# vcf.net
KiCad netlist of a schematic drawn in EAGLE
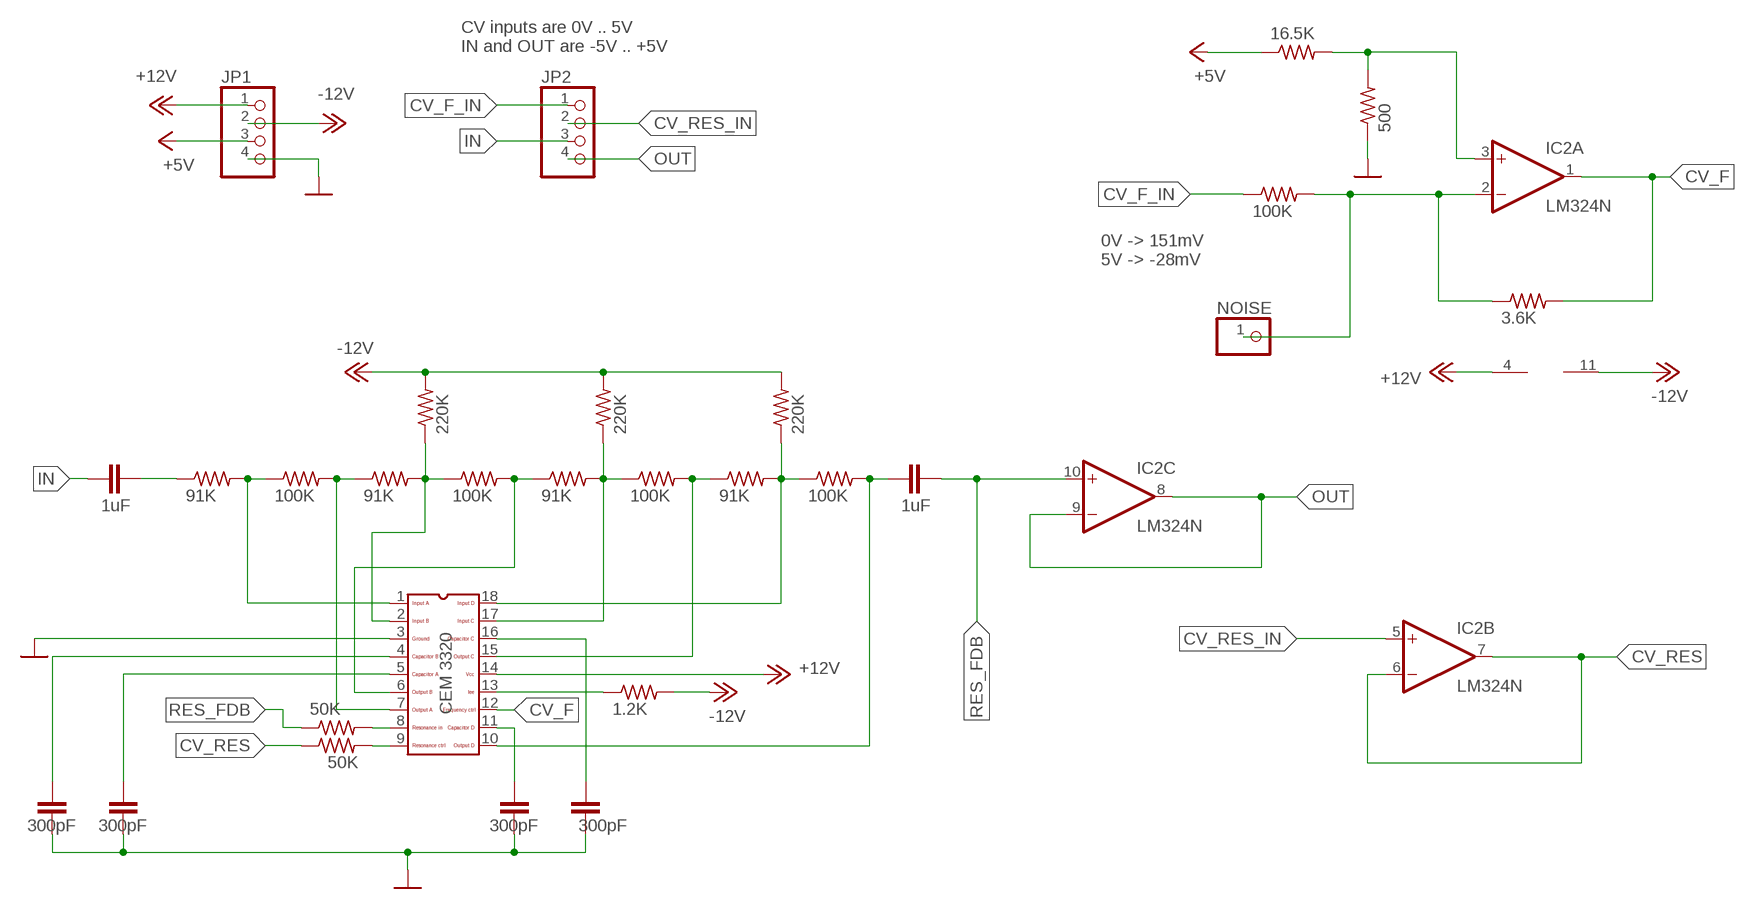
[diagram p0: schematic, sheet 1]

(export (version "E")
  (design (tool "Eeschema 10.0.6"))
  (components
    (comp (ref "C1")
      (value "300pF")
      (footprint "eagle-import:C025-030X050")
      (libsource (lib "eagle-import") (part "C-EU025-030X050"))
    )
    (comp (ref "C2")
      (value "300pF")
      (footprint "eagle-import:C025-030X050")
      (libsource (lib "eagle-import") (part "C-EU025-030X050"))
    )
    (comp (ref "C3")
      (value "300pF")
      (footprint "eagle-import:C025-030X050")
      (libsource (lib "eagle-import") (part "C-EU025-030X050"))
    )
    (comp (ref "C4")
      (value "300pF")
      (footprint "eagle-import:C025-030X050")
      (libsource (lib "eagle-import") (part "C-EU025-030X050"))
    )
    (comp (ref "C5")
      (value "1uF")
      (footprint "eagle-import:C025-030X050")
      (libsource (lib "eagle-import") (part "C-EU025-030X050"))
    )
    (comp (ref "C6")
      (value "1uF")
      (footprint "eagle-import:C025-030X050")
      (libsource (lib "eagle-import") (part "C-EU025-030X050"))
    )
    (comp (ref "IC1")
      (value "CEM3320")
      (footprint "eagle-import:DIL18")
      (libsource (lib "eagle-import") (part "CEM3320"))
    )
    (comp (ref "IC2")
      (value "LM324N")
      (footprint "eagle-import:DIL14")
      (libsource (lib "eagle-import") (part "LM324N"))
    )
    (comp (ref "JP1")
      (value "PINHD-1X4")
      (footprint "eagle-import:1X04")
      (libsource (lib "eagle-import") (part "PINHD-1X4"))
    )
    (comp (ref "JP2")
      (value "PINHD-1X4")
      (footprint "eagle-import:1X04")
      (libsource (lib "eagle-import") (part "PINHD-1X4"))
    )
    (comp (ref "NOISE")
      (value "PINHD-1X1")
      (footprint "eagle-import:1X01")
      (libsource (lib "eagle-import") (part "PINHD-1X1"))
    )
    (comp (ref "R1")
      (value "1.2K")
      (footprint "eagle-import:0204_7")
      (libsource (lib "eagle-import") (part "R-US_0204/7"))
    )
    (comp (ref "R2")
      (value "91K")
      (footprint "eagle-import:0204_7")
      (libsource (lib "eagle-import") (part "R-US_0204/7"))
    )
    (comp (ref "R3")
      (value "100K")
      (footprint "eagle-import:0204_7")
      (libsource (lib "eagle-import") (part "R-US_0204/7"))
    )
    (comp (ref "R4")
      (value "91K")
      (footprint "eagle-import:0204_7")
      (libsource (lib "eagle-import") (part "R-US_0204/7"))
    )
    (comp (ref "R5")
      (value "100K")
      (footprint "eagle-import:0204_7")
      (libsource (lib "eagle-import") (part "R-US_0204/7"))
    )
    (comp (ref "R6")
      (value "91K")
      (footprint "eagle-import:0204_7")
      (libsource (lib "eagle-import") (part "R-US_0204/7"))
    )
    (comp (ref "R7")
      (value "100K")
      (footprint "eagle-import:0204_7")
      (libsource (lib "eagle-import") (part "R-US_0204/7"))
    )
    (comp (ref "R8")
      (value "91K")
      (footprint "eagle-import:0204_7")
      (libsource (lib "eagle-import") (part "R-US_0204/7"))
    )
    (comp (ref "R9")
      (value "100K")
      (footprint "eagle-import:0204_7")
      (libsource (lib "eagle-import") (part "R-US_0204/7"))
    )
    (comp (ref "R10")
      (value "220K")
      (footprint "eagle-import:0204_7")
      (libsource (lib "eagle-import") (part "R-US_0204/7"))
    )
    (comp (ref "R11")
      (value "220K")
      (footprint "eagle-import:0204_7")
      (libsource (lib "eagle-import") (part "R-US_0204/7"))
    )
    (comp (ref "R12")
      (value "220K")
      (footprint "eagle-import:0204_7")
      (libsource (lib "eagle-import") (part "R-US_0204/7"))
    )
    (comp (ref "R13")
      (value "16.5K")
      (footprint "eagle-import:0204_7")
      (libsource (lib "eagle-import") (part "R-US_0204/7"))
    )
    (comp (ref "R14")
      (value "500")
      (footprint "eagle-import:0204_7")
      (libsource (lib "eagle-import") (part "R-US_0204/7"))
    )
    (comp (ref "R15")
      (value "100K")
      (footprint "eagle-import:0204_7")
      (libsource (lib "eagle-import") (part "R-US_0204/7"))
    )
    (comp (ref "R16")
      (value "3.6K")
      (footprint "eagle-import:0204_7")
      (libsource (lib "eagle-import") (part "R-US_0204/7"))
    )
    (comp (ref "R17")
      (value "50K")
      (footprint "eagle-import:0204_7")
      (libsource (lib "eagle-import") (part "R-US_0204/7"))
    )
    (comp (ref "R18")
      (value "50K")
      (footprint "eagle-import:0204_7")
      (libsource (lib "eagle-import") (part "R-US_0204/7"))
    )
  )
  (nets
    (net (code "1") (name "+5V") (class "Default")
      (node (ref "JP1") (pin "3") (pinfunction "3_3") (pintype "passive"))
      (node (ref "R13") (pin "1") (pinfunction "1_1") (pintype "passive"))
    )
    (net (code "2") (name "+12V") (class "Default")
      (node (ref "IC1") (pin "14") (pinfunction "14_14") (pintype "power_in"))
      (node (ref "IC2") (pin "4") (pinfunction "V+_4") (pintype "power_in"))
      (node (ref "JP1") (pin "1") (pinfunction "1_1") (pintype "passive"))
    )
    (net (code "3") (name "-12V") (class "Default")
      (node (ref "IC2") (pin "11") (pinfunction "V-_11") (pintype "power_in"))
      (node (ref "JP1") (pin "2") (pinfunction "2_2") (pintype "passive"))
      (node (ref "R1") (pin "2") (pinfunction "2_2") (pintype "passive"))
      (node (ref "R10") (pin "2") (pinfunction "2_2") (pintype "passive"))
      (node (ref "R11") (pin "2") (pinfunction "2_2") (pintype "passive"))
      (node (ref "R12") (pin "2") (pinfunction "2_2") (pintype "passive"))
    )
    (net (code "4") (name "CV_F") (class "Default")
      (node (ref "IC1") (pin "12") (pinfunction "12_12") (pintype "bidirectional"))
      (node (ref "IC2") (pin "1") (pinfunction "OUT_1") (pintype "output"))
      (node (ref "R16") (pin "2") (pinfunction "2_2") (pintype "passive"))
    )
    (net (code "5") (name "CV_F_IN") (class "Default")
      (node (ref "JP2") (pin "1") (pinfunction "1_1") (pintype "passive"))
      (node (ref "R15") (pin "1") (pinfunction "1_1") (pintype "passive"))
    )
    (net (code "6") (name "CV_RES") (class "Default")
      (node (ref "IC2") (pin "6") (pinfunction "-IN_6") (pintype "input"))
      (node (ref "IC2") (pin "7") (pinfunction "OUT_7") (pintype "output"))
      (node (ref "R18") (pin "1") (pinfunction "1_1") (pintype "passive"))
    )
    (net (code "7") (name "CV_RES_IN") (class "Default")
      (node (ref "IC2") (pin "5") (pinfunction "+IN_5") (pintype "input"))
      (node (ref "JP2") (pin "2") (pinfunction "2_2") (pintype "passive"))
    )
    (net (code "8") (name "GND") (class "Default")
      (node (ref "C1") (pin "2") (pinfunction "2_2") (pintype "passive"))
      (node (ref "C2") (pin "2") (pinfunction "2_2") (pintype "passive"))
      (node (ref "C3") (pin "2") (pinfunction "2_2") (pintype "passive"))
      (node (ref "C4") (pin "2") (pinfunction "2_2") (pintype "passive"))
      (node (ref "IC1") (pin "3") (pinfunction "3_3") (pintype "power_in"))
      (node (ref "JP1") (pin "4") (pinfunction "4_4") (pintype "passive"))
      (node (ref "R14") (pin "1") (pinfunction "1_1") (pintype "passive"))
    )
    (net (code "9") (name "IN") (class "Default")
      (node (ref "C6") (pin "1") (pinfunction "1_1") (pintype "passive"))
      (node (ref "JP2") (pin "3") (pinfunction "3_3") (pintype "passive"))
    )
    (net (code "10") (name "Net-(C1-Pad1)") (class "Default")
      (node (ref "C1") (pin "1") (pinfunction "1_1") (pintype "passive"))
      (node (ref "IC1") (pin "11") (pinfunction "11_11") (pintype "output"))
    )
    (net (code "11") (name "Net-(C2-Pad1)") (class "Default")
      (node (ref "C2") (pin "1") (pinfunction "1_1") (pintype "passive"))
      (node (ref "IC1") (pin "16") (pinfunction "16_16") (pintype "bidirectional"))
    )
    (net (code "12") (name "Net-(C3-Pad1)") (class "Default")
      (node (ref "C3") (pin "1") (pinfunction "1_1") (pintype "passive"))
      (node (ref "IC1") (pin "5") (pinfunction "5_5") (pintype "bidirectional"))
    )
    (net (code "13") (name "Net-(C4-Pad1)") (class "Default")
      (node (ref "C4") (pin "1") (pinfunction "1_1") (pintype "passive"))
      (node (ref "IC1") (pin "4") (pinfunction "4_4") (pintype "bidirectional"))
    )
    (net (code "14") (name "Net-(C5-Pad1)") (class "Default")
      (node (ref "C5") (pin "1") (pinfunction "1_1") (pintype "passive"))
      (node (ref "IC1") (pin "10") (pinfunction "10_10") (pintype "output"))
      (node (ref "R9") (pin "2") (pinfunction "2_2") (pintype "passive"))
    )
    (net (code "15") (name "Net-(C6-Pad2)") (class "Default")
      (node (ref "C6") (pin "2") (pinfunction "2_2") (pintype "passive"))
      (node (ref "R2") (pin "1") (pinfunction "1_1") (pintype "passive"))
    )
    (net (code "16") (name "Net-(IC1-Pad1)") (class "Default")
      (node (ref "IC1") (pin "1") (pinfunction "1_1") (pintype "input"))
      (node (ref "R2") (pin "2") (pinfunction "2_2") (pintype "passive"))
      (node (ref "R3") (pin "1") (pinfunction "1_1") (pintype "passive"))
    )
    (net (code "17") (name "Net-(IC1-Pad2)") (class "Default")
      (node (ref "IC1") (pin "2") (pinfunction "2_2") (pintype "input"))
      (node (ref "R11") (pin "1") (pinfunction "1_1") (pintype "passive"))
      (node (ref "R4") (pin "2") (pinfunction "2_2") (pintype "passive"))
      (node (ref "R5") (pin "1") (pinfunction "1_1") (pintype "passive"))
    )
    (net (code "18") (name "Net-(IC1-Pad6)") (class "Default")
      (node (ref "IC1") (pin "6") (pinfunction "6_6") (pintype "output"))
      (node (ref "R5") (pin "2") (pinfunction "2_2") (pintype "passive"))
      (node (ref "R6") (pin "1") (pinfunction "1_1") (pintype "passive"))
    )
    (net (code "19") (name "Net-(IC1-Pad7)") (class "Default")
      (node (ref "IC1") (pin "7") (pinfunction "7_7") (pintype "output"))
      (node (ref "R3") (pin "2") (pinfunction "2_2") (pintype "passive"))
      (node (ref "R4") (pin "1") (pinfunction "1_1") (pintype "passive"))
    )
    (net (code "20") (name "Net-(IC1-Pad8)") (class "Default")
      (node (ref "IC1") (pin "8") (pinfunction "8_8") (pintype "input"))
      (node (ref "R17") (pin "2") (pinfunction "2_2") (pintype "passive"))
    )
    (net (code "21") (name "Net-(IC1-Pad9)") (class "Default")
      (node (ref "IC1") (pin "9") (pinfunction "9_9") (pintype "input"))
      (node (ref "R18") (pin "2") (pinfunction "2_2") (pintype "passive"))
    )
    (net (code "22") (name "Net-(IC1-Pad13)") (class "Default")
      (node (ref "IC1") (pin "13") (pinfunction "13_13") (pintype "power_in"))
      (node (ref "R1") (pin "1") (pinfunction "1_1") (pintype "passive"))
    )
    (net (code "23") (name "Net-(IC1-Pad15)") (class "Default")
      (node (ref "IC1") (pin "15") (pinfunction "15_15") (pintype "output"))
      (node (ref "R7") (pin "2") (pinfunction "2_2") (pintype "passive"))
      (node (ref "R8") (pin "1") (pinfunction "1_1") (pintype "passive"))
    )
    (net (code "24") (name "Net-(IC1-Pad17)") (class "Default")
      (node (ref "IC1") (pin "17") (pinfunction "17_17") (pintype "input"))
      (node (ref "R10") (pin "1") (pinfunction "1_1") (pintype "passive"))
      (node (ref "R6") (pin "2") (pinfunction "2_2") (pintype "passive"))
      (node (ref "R7") (pin "1") (pinfunction "1_1") (pintype "passive"))
    )
    (net (code "25") (name "Net-(IC1-Pad18)") (class "Default")
      (node (ref "IC1") (pin "18") (pinfunction "18_18") (pintype "input"))
      (node (ref "R12") (pin "1") (pinfunction "1_1") (pintype "passive"))
      (node (ref "R8") (pin "2") (pinfunction "2_2") (pintype "passive"))
      (node (ref "R9") (pin "1") (pinfunction "1_1") (pintype "passive"))
    )
    (net (code "26") (name "Net-(IC2A-+IN)") (class "Default")
      (node (ref "IC2") (pin "3") (pinfunction "+IN_3") (pintype "input"))
      (node (ref "R13") (pin "2") (pinfunction "2_2") (pintype "passive"))
      (node (ref "R14") (pin "2") (pinfunction "2_2") (pintype "passive"))
    )
    (net (code "27") (name "Net-(IC2A--IN)") (class "Default")
      (node (ref "IC2") (pin "2") (pinfunction "-IN_2") (pintype "input"))
      (node (ref "NOISE") (pin "1") (pinfunction "1_1") (pintype "passive"))
      (node (ref "R15") (pin "2") (pinfunction "2_2") (pintype "passive"))
      (node (ref "R16") (pin "1") (pinfunction "1_1") (pintype "passive"))
    )
    (net (code "28") (name "OUT") (class "Default")
      (node (ref "IC2") (pin "8") (pinfunction "OUT_8") (pintype "output"))
      (node (ref "IC2") (pin "9") (pinfunction "-IN_9") (pintype "input"))
      (node (ref "JP2") (pin "4") (pinfunction "4_4") (pintype "passive"))
    )
    (net (code "29") (name "RES_FDB") (class "Default")
      (node (ref "C5") (pin "2") (pinfunction "2_2") (pintype "passive"))
      (node (ref "IC2") (pin "10") (pinfunction "+IN_10") (pintype "input"))
      (node (ref "R17") (pin "1") (pinfunction "1_1") (pintype "passive"))
    )
  )
)
